# uC.net
KiCad netlist of a schematic drawn in Altium Designer
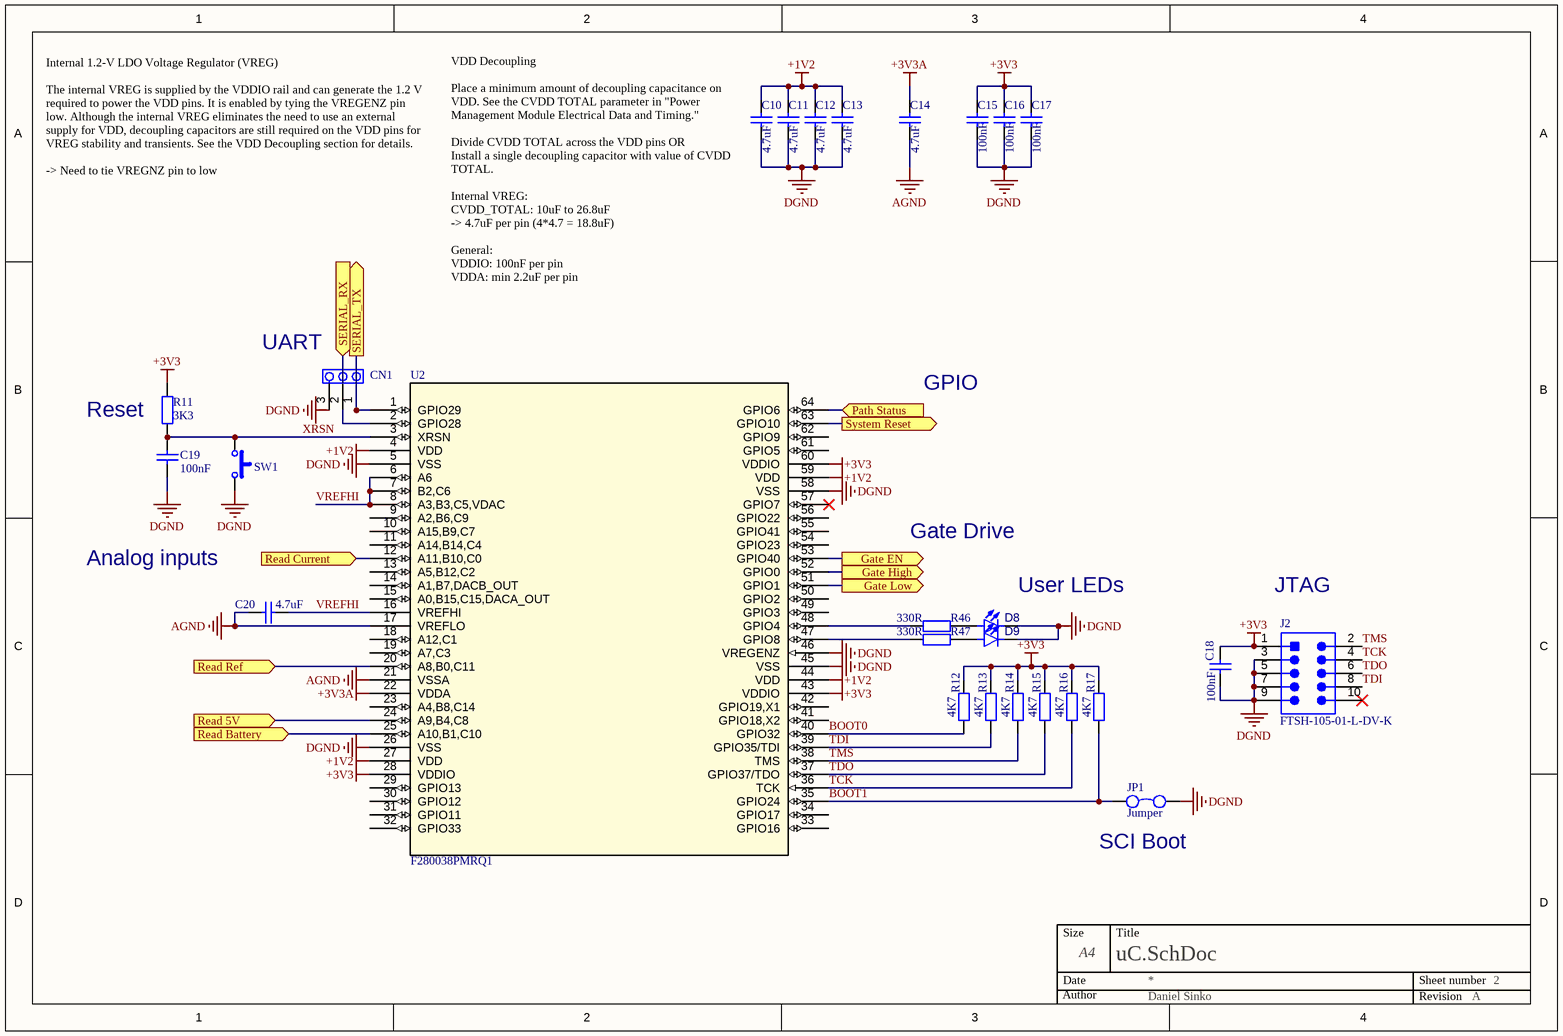
[diagram p0: uC.SchDoc]

(export (version "E")
  (design (tool "Eeschema 10.0.6"))
  (components
    (comp (ref "C10")
      (value "4.7uF")
      (footprint "CAP0603")
      (description "Capacitor Ceramic 4.7uF 10V X5R 10% 0603 T/R")
      (fields
        (field (name "MANUFACTURER") "Samsung")
        (field (name "MANUFACTURER PART NUMBER") "CL10A475KP8NNWC")
      )
      (libsource (lib "UPS_Schlib") (part "4.7uF"))
    )
    (comp (ref "C11")
      (value "4.7uF")
      (footprint "CAP0603")
      (description "Capacitor Ceramic 4.7uF 10V X5R 10% 0603 T/R")
      (fields
        (field (name "MANUFACTURER") "Samsung")
        (field (name "MANUFACTURER PART NUMBER") "CL10A475KP8NNWC")
      )
      (libsource (lib "UPS_Schlib") (part "4.7uF"))
    )
    (comp (ref "C12")
      (value "4.7uF")
      (footprint "CAP0603")
      (description "Capacitor Ceramic 4.7uF 10V X5R 10% 0603 T/R")
      (fields
        (field (name "MANUFACTURER") "Samsung")
        (field (name "MANUFACTURER PART NUMBER") "CL10A475KP8NNWC")
      )
      (libsource (lib "UPS_Schlib") (part "4.7uF"))
    )
    (comp (ref "C13")
      (value "4.7uF")
      (footprint "CAP0603")
      (description "Capacitor Ceramic 4.7uF 10V X5R 10% 0603 T/R")
      (fields
        (field (name "MANUFACTURER") "Samsung")
        (field (name "MANUFACTURER PART NUMBER") "CL10A475KP8NNWC")
      )
      (libsource (lib "UPS_Schlib") (part "4.7uF"))
    )
    (comp (ref "C14")
      (value "4.7uF")
      (footprint "CAP0603")
      (description "Capacitor Ceramic 4.7uF 10V X5R 10% 0603 T/R")
      (fields
        (field (name "MANUFACTURER") "Samsung")
        (field (name "MANUFACTURER PART NUMBER") "CL10A475KP8NNWC")
      )
      (libsource (lib "UPS_Schlib") (part "4.7uF"))
    )
    (comp (ref "C15")
      (value "100nF")
      (footprint "CAP0603")
      (fields
        (field (name "MANUFACTURER") "Samsung")
        (field (name "MANUFACTURER PART NUMBER") "CL10B104KA8WPNC")
      )
      (libsource (lib "UPS_Schlib") (part "100nF"))
    )
    (comp (ref "C16")
      (value "100nF")
      (footprint "CAP0603")
      (fields
        (field (name "MANUFACTURER") "Samsung")
        (field (name "MANUFACTURER PART NUMBER") "CL10B104KA8WPNC")
      )
      (libsource (lib "UPS_Schlib") (part "100nF"))
    )
    (comp (ref "C17")
      (value "100nF")
      (footprint "CAP0603")
      (fields
        (field (name "MANUFACTURER") "Samsung")
        (field (name "MANUFACTURER PART NUMBER") "CL10B104KA8WPNC")
      )
      (libsource (lib "UPS_Schlib") (part "100nF"))
    )
    (comp (ref "C18")
      (value "100nF")
      (footprint "CAP0603")
      (fields
        (field (name "MANUFACTURER") "Samsung")
        (field (name "MANUFACTURER PART NUMBER") "CL10B104KA8WPNC")
      )
      (libsource (lib "UPS_Schlib") (part "100nF"))
    )
    (comp (ref "C19")
      (value "100nF")
      (footprint "CAP0603")
      (fields
        (field (name "MANUFACTURER") "Samsung")
        (field (name "MANUFACTURER PART NUMBER") "CL10B104KA8WPNC")
      )
      (libsource (lib "UPS_Schlib") (part "100nF"))
    )
    (comp (ref "C20")
      (value "4.7uF")
      (footprint "CAP0603")
      (description "Capacitor Ceramic 4.7uF 10V X5R 10% 0603 T/R")
      (fields
        (field (name "MANUFACTURER") "Samsung")
        (field (name "MANUFACTURER PART NUMBER") "CL10A475KP8NNWC")
      )
      (libsource (lib "UPS_Schlib") (part "4.7uF"))
    )
    (comp (ref "CN1")
      (value "Pins 1x3")
      (footprint "PIN-1X3")
      (description "1x3 2.54mm")
      (libsource (lib "UPS_Schlib") (part "Pins 1x3"))
    )
    (comp (ref "D8")
      (value "~")
      (footprint "LED0603")
      (description "Single Color LED, Bright Green, Water Clear, 1.1mm")
      (fields
        (field (name "MANUFACTURER") "Wurth Electronics")
        (field (name "MANUFACTURER PART NUMBER") "150060VS75000")
      )
      (libsource (lib "UPS_Schlib") (part "LED Green"))
    )
    (comp (ref "D9")
      (value "~")
      (footprint "LED0603")
      (description "Single Color LED, Bright Green, Water Clear, 1.1mm")
      (fields
        (field (name "MANUFACTURER") "Wurth Electronics")
        (field (name "MANUFACTURER PART NUMBER") "150060VS75000")
      )
      (libsource (lib "UPS_Schlib") (part "LED Green"))
    )
    (comp (ref "J2")
      (value "FTSH-105-01-L-DV-K")
      (footprint "CON-2x5-1.27")
      (fields
        (field (name "MANUFACTURER") "Samtec")
        (field (name "MANUFACTURER PART NUMBER") "FTSH-105-01-L-DV-K-P-TR")
      )
      (libsource (lib "UPS_Schlib") (part "Connector_10Pin"))
    )
    (comp (ref "JP1")
      (value "Jumper")
      (footprint "PIN-1X2")
      (description "Interconnection Device")
      (fields (field (name "MANUFACTURER") "Harwin") (field (name "MANUFACTURER PART NUMBER") "M7582-46"))
      (libsource (lib "UPS_Schlib") (part "Jumper"))
    )
    (comp (ref "R11")
      (value "3K3")
      (footprint "RES0603")
      (fields
        (field (name "TOLERANCE") "1%")
        (field (name "POWER") "100mW")
        (field (name "MANUFACTURER") "Yageo")
      )
      (libsource (lib "UPS_Schlib") (part "3K3"))
    )
    (comp (ref "R12")
      (value "4K7")
      (footprint "RES0603")
      (fields
        (field (name "MANUFACTURER") "Yageo")
        (field (name "MANUFACTURER PART NUMBER") "AC0603FR-134K7L")
      )
      (libsource (lib "UPS_Schlib") (part "4K7"))
    )
    (comp (ref "R13")
      (value "4K7")
      (footprint "RES0603")
      (fields
        (field (name "MANUFACTURER") "Yageo")
        (field (name "MANUFACTURER PART NUMBER") "AC0603FR-134K7L")
      )
      (libsource (lib "UPS_Schlib") (part "4K7"))
    )
    (comp (ref "R14")
      (value "4K7")
      (footprint "RES0603")
      (fields
        (field (name "MANUFACTURER") "Yageo")
        (field (name "MANUFACTURER PART NUMBER") "AC0603FR-134K7L")
      )
      (libsource (lib "UPS_Schlib") (part "4K7"))
    )
    (comp (ref "R15")
      (value "4K7")
      (footprint "RES0603")
      (fields
        (field (name "MANUFACTURER") "Yageo")
        (field (name "MANUFACTURER PART NUMBER") "AC0603FR-134K7L")
      )
      (libsource (lib "UPS_Schlib") (part "4K7"))
    )
    (comp (ref "R16")
      (value "4K7")
      (footprint "RES0603")
      (fields
        (field (name "MANUFACTURER") "Yageo")
        (field (name "MANUFACTURER PART NUMBER") "AC0603FR-134K7L")
      )
      (libsource (lib "UPS_Schlib") (part "4K7"))
    )
    (comp (ref "R17")
      (value "4K7")
      (footprint "RES0603")
      (fields
        (field (name "MANUFACTURER") "Yageo")
        (field (name "MANUFACTURER PART NUMBER") "AC0603FR-134K7L")
      )
      (libsource (lib "UPS_Schlib") (part "4K7"))
    )
    (comp (ref "R46")
      (value "330R")
      (footprint "RES0603")
      (fields
        (field (name "MANUFACTURER") "Walsin Technologies")
        (field (name "MANUFACTURER PART NUMBER") "WR06X3300FTL")
      )
      (libsource (lib "UPS_Schlib") (part "330R"))
    )
    (comp (ref "R47")
      (value "330R")
      (footprint "RES0603")
      (fields
        (field (name "MANUFACTURER") "Walsin Technologies")
        (field (name "MANUFACTURER PART NUMBER") "WR06X3300FTL")
      )
      (libsource (lib "UPS_Schlib") (part "330R"))
    )
    (comp (ref "SW1")
      (value "PTS526 Button")
      (footprint "PTS526 SMG15J SMTR2 LFS")
      (description "PTS526 Series SPST-NO Off-Mom 160 gf Top Actuated J Lead SMT Tactile Switch")
      (fields
        (field (name "MANUFACTURER") "ITT C&K")
        (field (name "MANUFACTURER PART NUMBER") "PTS526SMG15JSMTR2LFS")
      )
      (libsource (lib "UPS_Schlib") (part "PTS526 Button"))
    )
    (comp (ref "U2")
      (value "F280038PMRQ1")
      (footprint "LQFP-64")
      (description "Automotive C2000™ 32-bit MCU 120-MHz 384-KB flash, FPU, TMU with CLA, AES and CAN-FD")
      (fields
        (field (name "MANUFACTURER") "Texas Instruments")
        (field (name "COPYRIGHT") "Copyright (C) 2023 Ultra Librarian. All rights reserved.")
      )
      (libsource (lib "UPS_Schlib") (part "F280038CPMRQ1"))
    )
  )
  (nets
    (net (code "1") (name "+1V2") (class "Default")
      (node (ref "C10") (pin "2") (pinfunction "2_2") (pintype "passive"))
      (node (ref "C11") (pin "2") (pinfunction "2_2") (pintype "passive"))
      (node (ref "C12") (pin "2") (pinfunction "2_2") (pintype "passive"))
      (node (ref "C13") (pin "2") (pinfunction "2_2") (pintype "passive"))
      (node (ref "U2") (pin "27") (pinfunction "VDD_27") (pintype "power_in"))
      (node (ref "U2") (pin "4") (pinfunction "VDD_4") (pintype "power_in"))
      (node (ref "U2") (pin "44") (pinfunction "VDD_44") (pintype "power_in"))
      (node (ref "U2") (pin "59") (pinfunction "VDD_59") (pintype "power_in"))
    )
    (net (code "2") (name "+3V3") (class "Default")
      (node (ref "C15") (pin "2") (pinfunction "2_2") (pintype "passive"))
      (node (ref "C16") (pin "2") (pinfunction "2_2") (pintype "passive"))
      (node (ref "C17") (pin "2") (pinfunction "2_2") (pintype "passive"))
      (node (ref "C18") (pin "2") (pinfunction "2_2") (pintype "passive"))
      (node (ref "J2") (pin "1") (pinfunction "1_1") (pintype "passive"))
      (node (ref "R11") (pin "2") (pinfunction "2_2") (pintype "passive"))
      (node (ref "R12") (pin "2") (pinfunction "2_2") (pintype "passive"))
      (node (ref "R13") (pin "2") (pinfunction "2_2") (pintype "passive"))
      (node (ref "R14") (pin "2") (pinfunction "2_2") (pintype "passive"))
      (node (ref "R15") (pin "2") (pinfunction "2_2") (pintype "passive"))
      (node (ref "R16") (pin "2") (pinfunction "2_2") (pintype "passive"))
      (node (ref "R17") (pin "2") (pinfunction "2_2") (pintype "passive"))
      (node (ref "U2") (pin "28") (pinfunction "VDDIO_28") (pintype "power_in"))
      (node (ref "U2") (pin "43") (pinfunction "VDDIO_43") (pintype "power_in"))
      (node (ref "U2") (pin "60") (pinfunction "VDDIO_60") (pintype "power_in"))
    )
    (net (code "3") (name "+3V3A") (class "Default")
      (node (ref "C14") (pin "2") (pinfunction "2_2") (pintype "passive"))
      (node (ref "U2") (pin "22") (pinfunction "VDDA_22") (pintype "power_in"))
    )
    (net (code "4") (name "/BOOT0") (class "Default")
      (node (ref "R12") (pin "1") (pinfunction "1_1") (pintype "passive"))
      (node (ref "U2") (pin "40") (pinfunction "GPIO32_40") (pintype "bidirectional"))
    )
    (net (code "5") (name "/BOOT1") (class "Default")
      (node (ref "JP1") (pin "1") (pintype "passive"))
      (node (ref "R17") (pin "1") (pinfunction "1_1") (pintype "passive"))
      (node (ref "U2") (pin "35") (pinfunction "GPIO24_35") (pintype "bidirectional"))
    )
    (net (code "6") (name "/Gate EN") (class "Default")
      (node (ref "U2") (pin "53") (pinfunction "GPIO40_53") (pintype "bidirectional"))
    )
    (net (code "7") (name "/Gate High") (class "Default")
      (node (ref "U2") (pin "52") (pinfunction "GPIO0_52") (pintype "bidirectional"))
    )
    (net (code "8") (name "/Gate Low") (class "Default")
      (node (ref "U2") (pin "51") (pinfunction "GPIO1_51") (pintype "bidirectional"))
    )
    (net (code "9") (name "/Path Status") (class "Default")
      (node (ref "U2") (pin "64") (pinfunction "GPIO6_64") (pintype "bidirectional"))
    )
    (net (code "10") (name "/Read 5V") (class "Default")
      (node (ref "U2") (pin "24") (pinfunction "A9,B4,C8_24") (pintype "bidirectional"))
    )
    (net (code "11") (name "/Read Battery") (class "Default")
      (node (ref "U2") (pin "25") (pinfunction "A10,B1,C10_25") (pintype "bidirectional"))
    )
    (net (code "12") (name "/Read Current") (class "Default")
      (node (ref "U2") (pin "12") (pinfunction "A11,B10,C0_12") (pintype "bidirectional"))
    )
    (net (code "13") (name "/Read Ref") (class "Default")
      (node (ref "U2") (pin "20") (pinfunction "A8,B0,C11_20") (pintype "bidirectional"))
    )
    (net (code "15") (name "/SERIAL_TX") (class "Default")
      (node (ref "CN1") (pin "1") (pinfunction "1_1") (pintype "passive"))
      (node (ref "U2") (pin "1") (pinfunction "GPIO29_1") (pintype "bidirectional"))
    )
    (net (code "16") (name "/System Reset") (class "Default")
      (node (ref "U2") (pin "63") (pinfunction "GPIO10_63") (pintype "bidirectional"))
    )
    (net (code "17") (name "/TCK") (class "Default")
      (node (ref "J2") (pin "4") (pinfunction "4_4") (pintype "passive"))
      (node (ref "R16") (pin "1") (pinfunction "1_1") (pintype "passive"))
      (node (ref "U2") (pin "36") (pinfunction "TCK_36") (pintype "input"))
    )
    (net (code "18") (name "/TDI") (class "Default")
      (node (ref "J2") (pin "8") (pinfunction "8_8") (pintype "passive"))
      (node (ref "R13") (pin "1") (pinfunction "1_1") (pintype "passive"))
      (node (ref "U2") (pin "39") (pinfunction "GPIO35/TDI_39") (pintype "bidirectional"))
    )
    (net (code "19") (name "/TDO") (class "Default")
      (node (ref "J2") (pin "6") (pinfunction "6_6") (pintype "passive"))
      (node (ref "R15") (pin "1") (pinfunction "1_1") (pintype "passive"))
      (node (ref "U2") (pin "37") (pinfunction "GPIO37/TDO_37") (pintype "bidirectional"))
    )
    (net (code "20") (name "/TMS") (class "Default")
      (node (ref "J2") (pin "2") (pinfunction "2_2") (pintype "passive"))
      (node (ref "R14") (pin "1") (pinfunction "1_1") (pintype "passive"))
      (node (ref "U2") (pin "38") (pinfunction "TMS_38") (pintype "bidirectional"))
    )
    (net (code "21") (name "/VREFHI") (class "Default")
      (node (ref "C20") (pin "2") (pinfunction "2_2") (pintype "passive"))
      (node (ref "U2") (pin "16") (pinfunction "VREFHI_16") (pintype "power_in"))
      (node (ref "U2") (pin "6") (pinfunction "A6_6") (pintype "bidirectional"))
      (node (ref "U2") (pin "7") (pinfunction "B2,C6_7") (pintype "bidirectional"))
      (node (ref "U2") (pin "8") (pinfunction "A3,B3,C5,VDAC_8") (pintype "bidirectional"))
    )
    (net (code "22") (name "/XRSN") (class "Default")
      (node (ref "C19") (pin "1") (pinfunction "1_1") (pintype "passive"))
      (node (ref "R11") (pin "1") (pinfunction "1_1") (pintype "passive"))
      (node (ref "SW1") (pin "2") (pinfunction "2_2") (pintype "passive"))
      (node (ref "U2") (pin "3") (pinfunction "XRSN_3") (pintype "bidirectional"))
    )
    (net (code "23") (name "AGND") (class "Default")
      (node (ref "C14") (pin "1") (pinfunction "1_1") (pintype "passive"))
      (node (ref "C20") (pin "1") (pinfunction "1_1") (pintype "passive"))
      (node (ref "U2") (pin "17") (pinfunction "VREFLO_17") (pintype "power_in"))
      (node (ref "U2") (pin "21") (pinfunction "VSSA_21") (pintype "power_in"))
    )
    (net (code "24") (name "DGND") (class "Default")
      (node (ref "C10") (pin "1") (pinfunction "1_1") (pintype "passive"))
      (node (ref "C11") (pin "1") (pinfunction "1_1") (pintype "passive"))
      (node (ref "C12") (pin "1") (pinfunction "1_1") (pintype "passive"))
      (node (ref "C13") (pin "1") (pinfunction "1_1") (pintype "passive"))
      (node (ref "C15") (pin "1") (pinfunction "1_1") (pintype "passive"))
      (node (ref "C16") (pin "1") (pinfunction "1_1") (pintype "passive"))
      (node (ref "C17") (pin "1") (pinfunction "1_1") (pintype "passive"))
      (node (ref "C18") (pin "1") (pinfunction "1_1") (pintype "passive"))
      (node (ref "C19") (pin "2") (pinfunction "2_2") (pintype "passive"))
      (node (ref "CN1") (pin "3") (pinfunction "3_3") (pintype "passive"))
      (node (ref "D8") (pin "1") (pinfunction "K_1") (pintype "passive"))
      (node (ref "D9") (pin "1") (pinfunction "K_1") (pintype "passive"))
      (node (ref "J2") (pin "3") (pinfunction "3_3") (pintype "passive"))
      (node (ref "J2") (pin "5") (pinfunction "5_5") (pintype "passive"))
      (node (ref "J2") (pin "7") (pinfunction "7_7") (pintype "passive"))
      (node (ref "J2") (pin "9") (pinfunction "9_9") (pintype "passive"))
      (node (ref "JP1") (pin "2") (pintype "passive"))
      (node (ref "SW1") (pin "1") (pinfunction "1_1") (pintype "passive"))
      (node (ref "U2") (pin "26") (pinfunction "VSS_26") (pintype "power_in"))
      (node (ref "U2") (pin "45") (pinfunction "VSS_45") (pintype "power_in"))
      (node (ref "U2") (pin "46") (pinfunction "VREGENZ_46") (pintype "input"))
      (node (ref "U2") (pin "5") (pinfunction "VSS_5") (pintype "power_in"))
      (node (ref "U2") (pin "58") (pinfunction "VSS_58") (pintype "power_in"))
    )
    (net (code "25") (name "Net-(D8-A)") (class "Default")
      (node (ref "D8") (pin "2") (pinfunction "A_2") (pintype "passive"))
      (node (ref "R46") (pin "1") (pinfunction "1_1") (pintype "passive"))
    )
    (net (code "26") (name "Net-(D9-A)") (class "Default")
      (node (ref "D9") (pin "2") (pinfunction "A_2") (pintype "passive"))
      (node (ref "R47") (pin "1") (pinfunction "1_1") (pintype "passive"))
    )
    (net (code "27") (name "Net-(U2-GPIO4)") (class "Default")
      (node (ref "R46") (pin "2") (pinfunction "2_2") (pintype "passive"))
      (node (ref "U2") (pin "48") (pinfunction "GPIO4_48") (pintype "bidirectional"))
    )
    (net (code "28") (name "Net-(U2-GPIO8)") (class "Default")
      (node (ref "R47") (pin "2") (pinfunction "2_2") (pintype "passive"))
      (node (ref "U2") (pin "47") (pinfunction "GPIO8_47") (pintype "bidirectional"))
    )
    (net (code "29") (name "Net-(U2-GPIO28)") (class "Default")
      (node (ref "CN1") (pin "2") (pinfunction "2_2") (pintype "passive"))
      (node (ref "U2") (pin "2") (pinfunction "GPIO28_2") (pintype "bidirectional"))
    )
    (net (code "30") (name "unconnected-(J2-Pad10)") (class "Default")
      (node (ref "J2") (pin "10") (pinfunction "10_10") (pintype "passive+no_connect"))
    )
    (net (code "31") (name "unconnected-(U2-A0,B15,C15,DACA_OUT-Pad15)") (class "Default")
      (node (ref "U2") (pin "15") (pinfunction "A0,B15,C15,DACA_OUT_15") (pintype "bidirectional"))
    )
    (net (code "32") (name "unconnected-(U2-A1,B7,DACB_OUT-Pad14)") (class "Default")
      (node (ref "U2") (pin "14") (pinfunction "A1,B7,DACB_OUT_14") (pintype "bidirectional"))
    )
    (net (code "33") (name "unconnected-(U2-A2,B6,C9-Pad9)") (class "Default")
      (node (ref "U2") (pin "9") (pinfunction "A2,B6,C9_9") (pintype "bidirectional"))
    )
    (net (code "34") (name "unconnected-(U2-A4,B8,C14-Pad23)") (class "Default")
      (node (ref "U2") (pin "23") (pinfunction "A4,B8,C14_23") (pintype "bidirectional"))
    )
    (net (code "35") (name "unconnected-(U2-A5,B12,C2-Pad13)") (class "Default")
      (node (ref "U2") (pin "13") (pinfunction "A5,B12,C2_13") (pintype "bidirectional"))
    )
    (net (code "36") (name "unconnected-(U2-A7,C3-Pad19)") (class "Default")
      (node (ref "U2") (pin "19") (pinfunction "A7,C3_19") (pintype "bidirectional"))
    )
    (net (code "37") (name "unconnected-(U2-A12,C1-Pad18)") (class "Default")
      (node (ref "U2") (pin "18") (pinfunction "A12,C1_18") (pintype "bidirectional"))
    )
    (net (code "38") (name "unconnected-(U2-A14,B14,C4-Pad11)") (class "Default")
      (node (ref "U2") (pin "11") (pinfunction "A14,B14,C4_11") (pintype "bidirectional"))
    )
    (net (code "39") (name "unconnected-(U2-A15,B9,C7-Pad10)") (class "Default")
      (node (ref "U2") (pin "10") (pinfunction "A15,B9,C7_10") (pintype "bidirectional"))
    )
    (net (code "40") (name "unconnected-(U2-GPIO2-Pad50)") (class "Default")
      (node (ref "U2") (pin "50") (pinfunction "GPIO2_50") (pintype "bidirectional"))
    )
    (net (code "41") (name "unconnected-(U2-GPIO3-Pad49)") (class "Default")
      (node (ref "U2") (pin "49") (pinfunction "GPIO3_49") (pintype "bidirectional"))
    )
    (net (code "42") (name "unconnected-(U2-GPIO5-Pad61)") (class "Default")
      (node (ref "U2") (pin "61") (pinfunction "GPIO5_61") (pintype "bidirectional"))
    )
    (net (code "43") (name "unconnected-(U2-GPIO7-Pad57)") (class "Default")
      (node (ref "U2") (pin "57") (pinfunction "GPIO7_57") (pintype "bidirectional+no_connect"))
    )
    (net (code "44") (name "unconnected-(U2-GPIO9-Pad62)") (class "Default")
      (node (ref "U2") (pin "62") (pinfunction "GPIO9_62") (pintype "bidirectional"))
    )
    (net (code "45") (name "unconnected-(U2-GPIO11-Pad31)") (class "Default")
      (node (ref "U2") (pin "31") (pinfunction "GPIO11_31") (pintype "bidirectional"))
    )
    (net (code "46") (name "unconnected-(U2-GPIO12-Pad30)") (class "Default")
      (node (ref "U2") (pin "30") (pinfunction "GPIO12_30") (pintype "bidirectional"))
    )
    (net (code "47") (name "unconnected-(U2-GPIO13-Pad29)") (class "Default")
      (node (ref "U2") (pin "29") (pinfunction "GPIO13_29") (pintype "bidirectional"))
    )
    (net (code "48") (name "unconnected-(U2-GPIO16-Pad33)") (class "Default")
      (node (ref "U2") (pin "33") (pinfunction "GPIO16_33") (pintype "bidirectional"))
    )
    (net (code "49") (name "unconnected-(U2-GPIO17-Pad34)") (class "Default")
      (node (ref "U2") (pin "34") (pinfunction "GPIO17_34") (pintype "bidirectional"))
    )
    (net (code "50") (name "unconnected-(U2-GPIO18,X2-Pad41)") (class "Default")
      (node (ref "U2") (pin "41") (pinfunction "GPIO18,X2_41") (pintype "bidirectional"))
    )
    (net (code "51") (name "unconnected-(U2-GPIO19,X1-Pad42)") (class "Default")
      (node (ref "U2") (pin "42") (pinfunction "GPIO19,X1_42") (pintype "bidirectional"))
    )
    (net (code "52") (name "unconnected-(U2-GPIO22-Pad56)") (class "Default")
      (node (ref "U2") (pin "56") (pinfunction "GPIO22_56") (pintype "bidirectional"))
    )
    (net (code "53") (name "unconnected-(U2-GPIO23-Pad54)") (class "Default")
      (node (ref "U2") (pin "54") (pinfunction "GPIO23_54") (pintype "bidirectional"))
    )
    (net (code "54") (name "unconnected-(U2-GPIO33-Pad32)") (class "Default")
      (node (ref "U2") (pin "32") (pinfunction "GPIO33_32") (pintype "bidirectional"))
    )
    (net (code "55") (name "unconnected-(U2-GPIO41-Pad55)") (class "Default")
      (node (ref "U2") (pin "55") (pinfunction "GPIO41_55") (pintype "bidirectional"))
    )
  )
)
